# dcb_single_input.net
KiCad netlist of a schematic drawn in Altium Designer
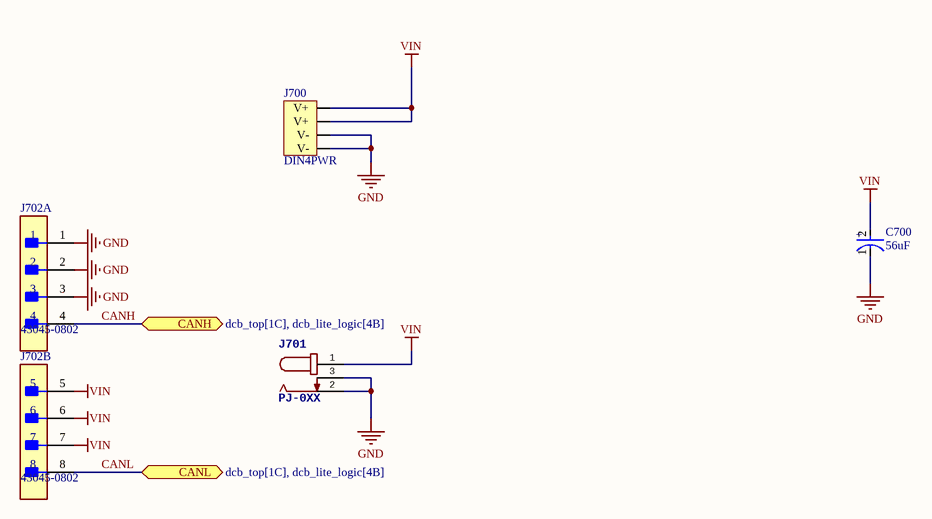
[diagram p0: dcb_single_input.SchDoc]

(export (version "E")
  (design (tool "Eeschema 10.0.6"))
  (components
    (comp (ref "C700")
      (value "56uF")
      (footprint "FP-FKG-MFG")
      (description "Cap Aluminum 56uF 63V 20% (10 X 10.2mm) SMD 0.03 Ohm 1800mA 5000h 105 C Embossed T/R")
      (fields (field (name "TOLERANCE") "20%") (field (name "VOLTAGE") "63V"))
      (libsource (lib "StackFoundry LLC") (part "203bc49f2ac43e59fd269a8c329ed05"))
    )
    (comp (ref "J700")
      (value "DIN4PWR")
      (footprint "PD40S")
      (libsource (lib "StackFoundry LLC") (part "DIN4PWR"))
    )
    (comp (ref "J701")
      (value "PJ-0XX")
      (footprint "CUI-PJ-002A_V")
      (description "2.0 x 6.5 mm, 2.5 A, Horizontal, Through Hole, Dc Power Jack Connector")
      (libsource (lib "StackFoundry LLC") (part "Symbol"))
    )
    (comp (ref "J702")
      (value "43045-0802")
      (footprint "FP-43045-0802-MFG")
      (description "Conn, Rect/PCB, Header, Rt Angle, 2 Row, 8 Pos, Micro-Fit 3.0, Gold, SMT, GlowWire Comp.")
      (libsource (lib "StackFoundry LLC") (part "85438c39ca9ef07d43bb2e97c52bc44"))
    )
  )
  (nets
    (net (code "1") (name "/CANH") (class "Default")
      (node (ref "J702") (pin "4") (pinfunction "4_4") (pintype "passive"))
    )
    (net (code "2") (name "/CANL") (class "Default")
      (node (ref "J702") (pin "8") (pinfunction "8_8") (pintype "passive"))
    )
    (net (code "3") (name "GND") (class "Default")
      (node (ref "C700") (pin "1") (pinfunction "C_1") (pintype "passive"))
      (node (ref "J700") (pin "1") (pinfunction "V-_1") (pintype "power_in"))
      (node (ref "J700") (pin "3") (pinfunction "V-_3") (pintype "power_in"))
      (node (ref "J701") (pin "2") (pinfunction "2_2") (pintype "passive"))
      (node (ref "J701") (pin "3") (pinfunction "3_3") (pintype "passive"))
      (node (ref "J702") (pin "1") (pinfunction "1_1") (pintype "passive"))
      (node (ref "J702") (pin "2") (pinfunction "2_2") (pintype "passive"))
      (node (ref "J702") (pin "3") (pinfunction "3_3") (pintype "passive"))
    )
    (net (code "4") (name "VIN") (class "Default")
      (node (ref "C700") (pin "2") (pinfunction "A_2") (pintype "passive"))
      (node (ref "J700") (pin "2") (pinfunction "V+_2") (pintype "power_in"))
      (node (ref "J700") (pin "4") (pinfunction "V+_4") (pintype "power_in"))
      (node (ref "J701") (pin "1") (pinfunction "1_1") (pintype "passive"))
      (node (ref "J702") (pin "5") (pinfunction "5_5") (pintype "passive"))
      (node (ref "J702") (pin "6") (pinfunction "6_6") (pintype "passive"))
      (node (ref "J702") (pin "7") (pinfunction "7_7") (pintype "passive"))
    )
  )
)
